# led-cc-driver-mk-3_0.net
KiCad netlist of a schematic drawn in EAGLE
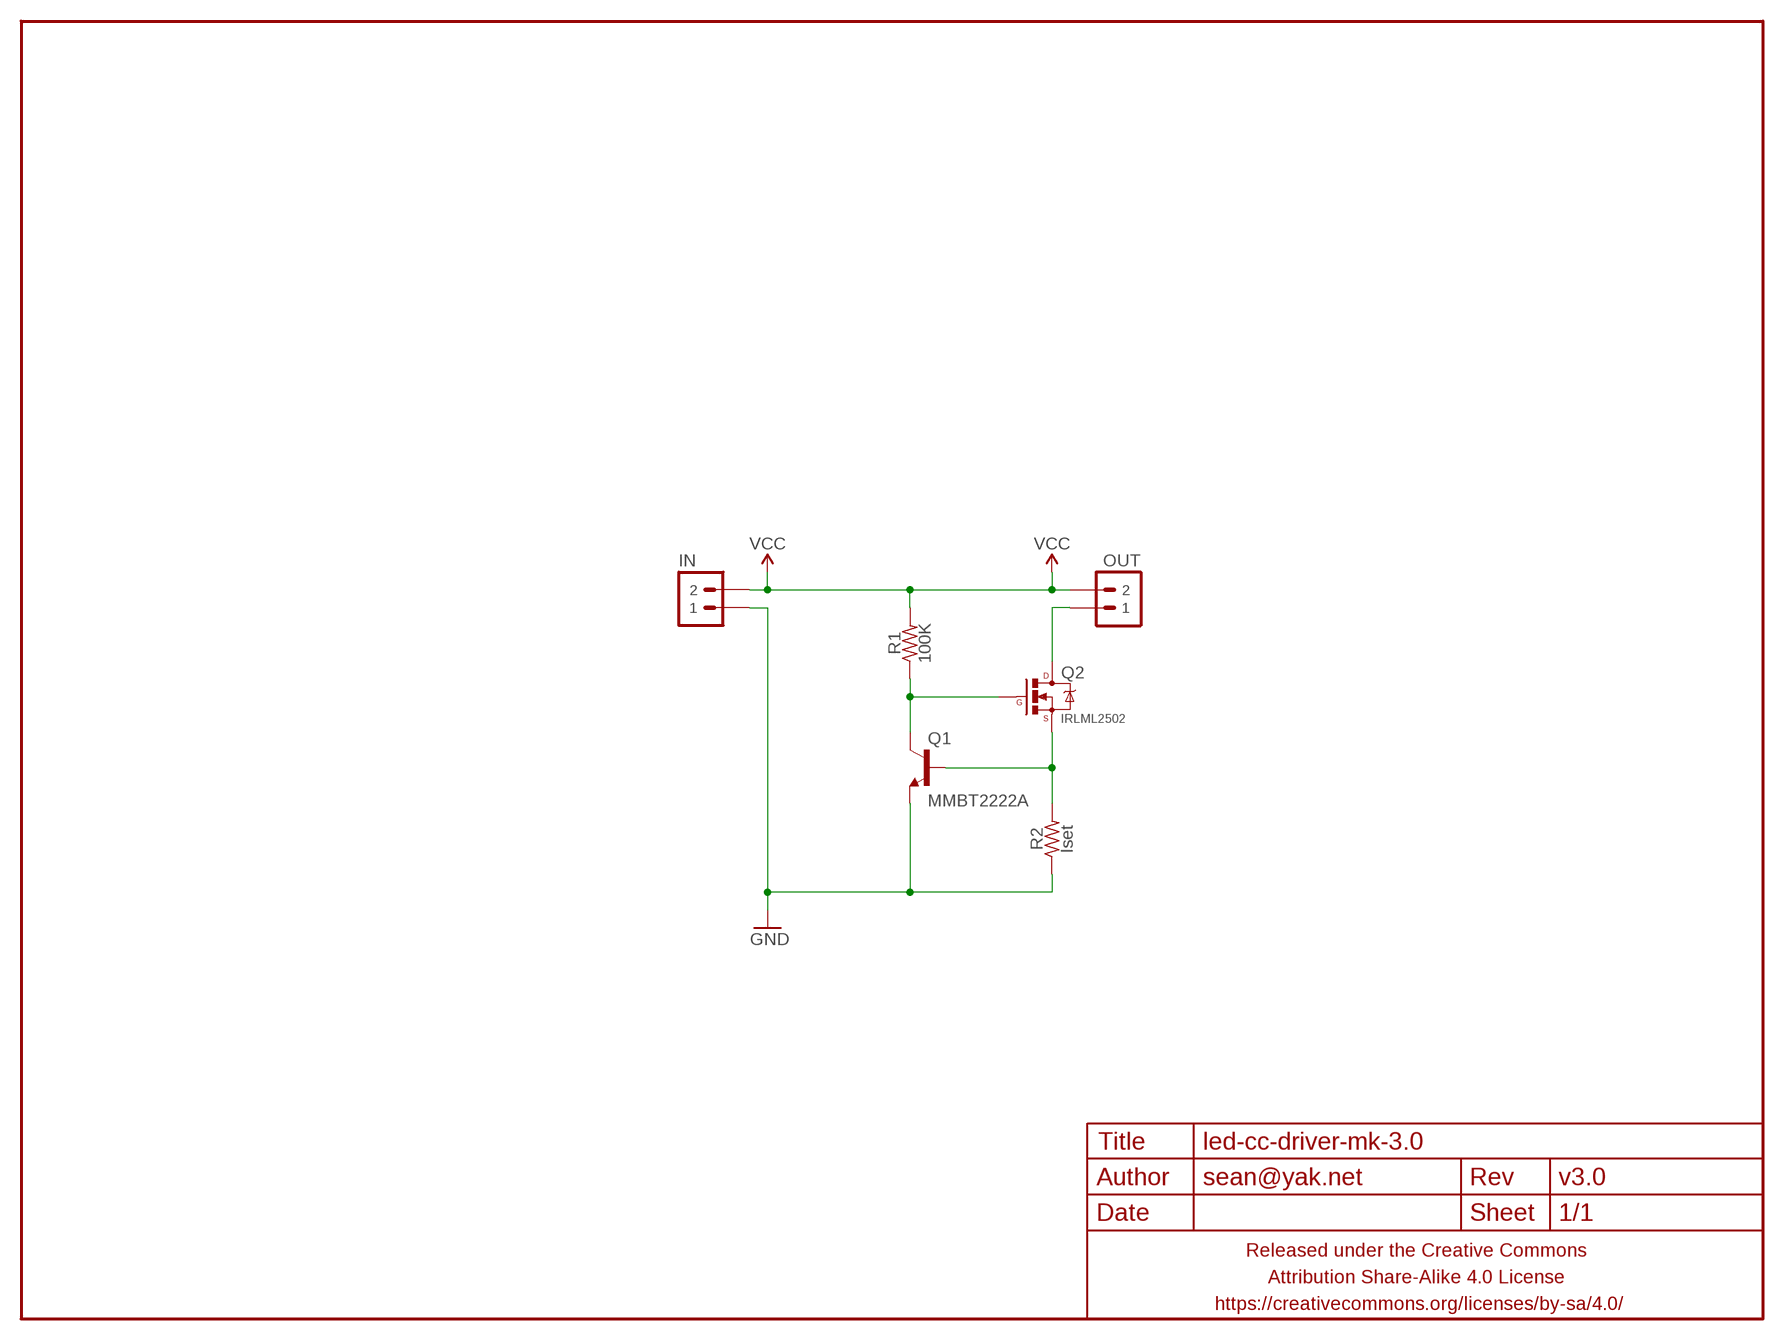
[diagram p0: schematic, sheet 1]

(export (version "E")
  (design (tool "Eeschema 10.0.6"))
  (components
    (comp (ref "FRAME1")
      (value "FRAME-LETTERNO_PACKAGE")
      (footprint "eagle-import:DUMMY")
      (fields (field (name "DESIGNER") "sean@yak.net") (field (name "VERSION") "v3.0"))
      (libsource (lib "eagle-import") (part "FRAME-LETTERNO_PACKAGE"))
    )
    (comp (ref "IN")
      (value "M02PTH-CENTERED")
      (footprint "eagle-import:1X02-CENTER")
      (libsource (lib "eagle-import") (part "M02PTH-CENTERED"))
    )
    (comp (ref "OUT")
      (value "M02PTH-CENTERED")
      (footprint "eagle-import:1X02-CENTER")
      (libsource (lib "eagle-import") (part "M02PTH-CENTERED"))
    )
    (comp (ref "Q1")
      (value "MMBT2222A")
      (footprint "eagle-import:SOT23")
      (libsource (lib "eagle-import") (part "TRANSISTOR_NPNMMBT2222A"))
    )
    (comp (ref "Q2")
      (value "IRLML2502")
      (footprint "eagle-import:SOT23")
      (libsource (lib "eagle-import") (part "MOSFET-NCHANNELIRLML2502"))
    )
    (comp (ref "R1")
      (value "100K")
      (footprint "eagle-import:R0603")
      (libsource (lib "eagle-import") (part "RESISTORR0603"))
    )
    (comp (ref "R2")
      (value "Iset")
      (footprint "eagle-import:R0603")
      (libsource (lib "eagle-import") (part "RESISTORR0603"))
    )
  )
  (nets
    (net (code "1") (name "GND") (class "Default")
      (node (ref "IN") (pin "1") (pinfunction "1_1") (pintype "passive"))
      (node (ref "Q1") (pin "2") (pinfunction "E_2") (pintype "passive"))
      (node (ref "R2") (pin "1") (pinfunction "1_1") (pintype "passive"))
    )
    (net (code "2") (name "Net-(Q1-B)") (class "Default")
      (node (ref "Q1") (pin "1") (pinfunction "B_1") (pintype "passive"))
      (node (ref "Q2") (pin "2") (pinfunction "S_2") (pintype "passive"))
      (node (ref "R2") (pin "2") (pinfunction "2_2") (pintype "passive"))
    )
    (net (code "3") (name "Net-(Q1-C)") (class "Default")
      (node (ref "Q1") (pin "3") (pinfunction "C_3") (pintype "passive"))
      (node (ref "Q2") (pin "1") (pinfunction "G_1") (pintype "passive"))
      (node (ref "R1") (pin "1") (pinfunction "1_1") (pintype "passive"))
    )
    (net (code "4") (name "Net-(Q2-D)") (class "Default")
      (node (ref "OUT") (pin "1") (pinfunction "1_1") (pintype "passive"))
      (node (ref "Q2") (pin "3") (pinfunction "D_3") (pintype "passive"))
    )
    (net (code "5") (name "VCC") (class "Default")
      (node (ref "IN") (pin "2") (pinfunction "2_2") (pintype "passive"))
      (node (ref "OUT") (pin "2") (pinfunction "2_2") (pintype "passive"))
      (node (ref "R1") (pin "2") (pinfunction "2_2") (pintype "passive"))
    )
  )
)
